# thruster_ctrl_and_pressure_sensor.net
KiCad netlist of a schematic drawn in Altium Designer
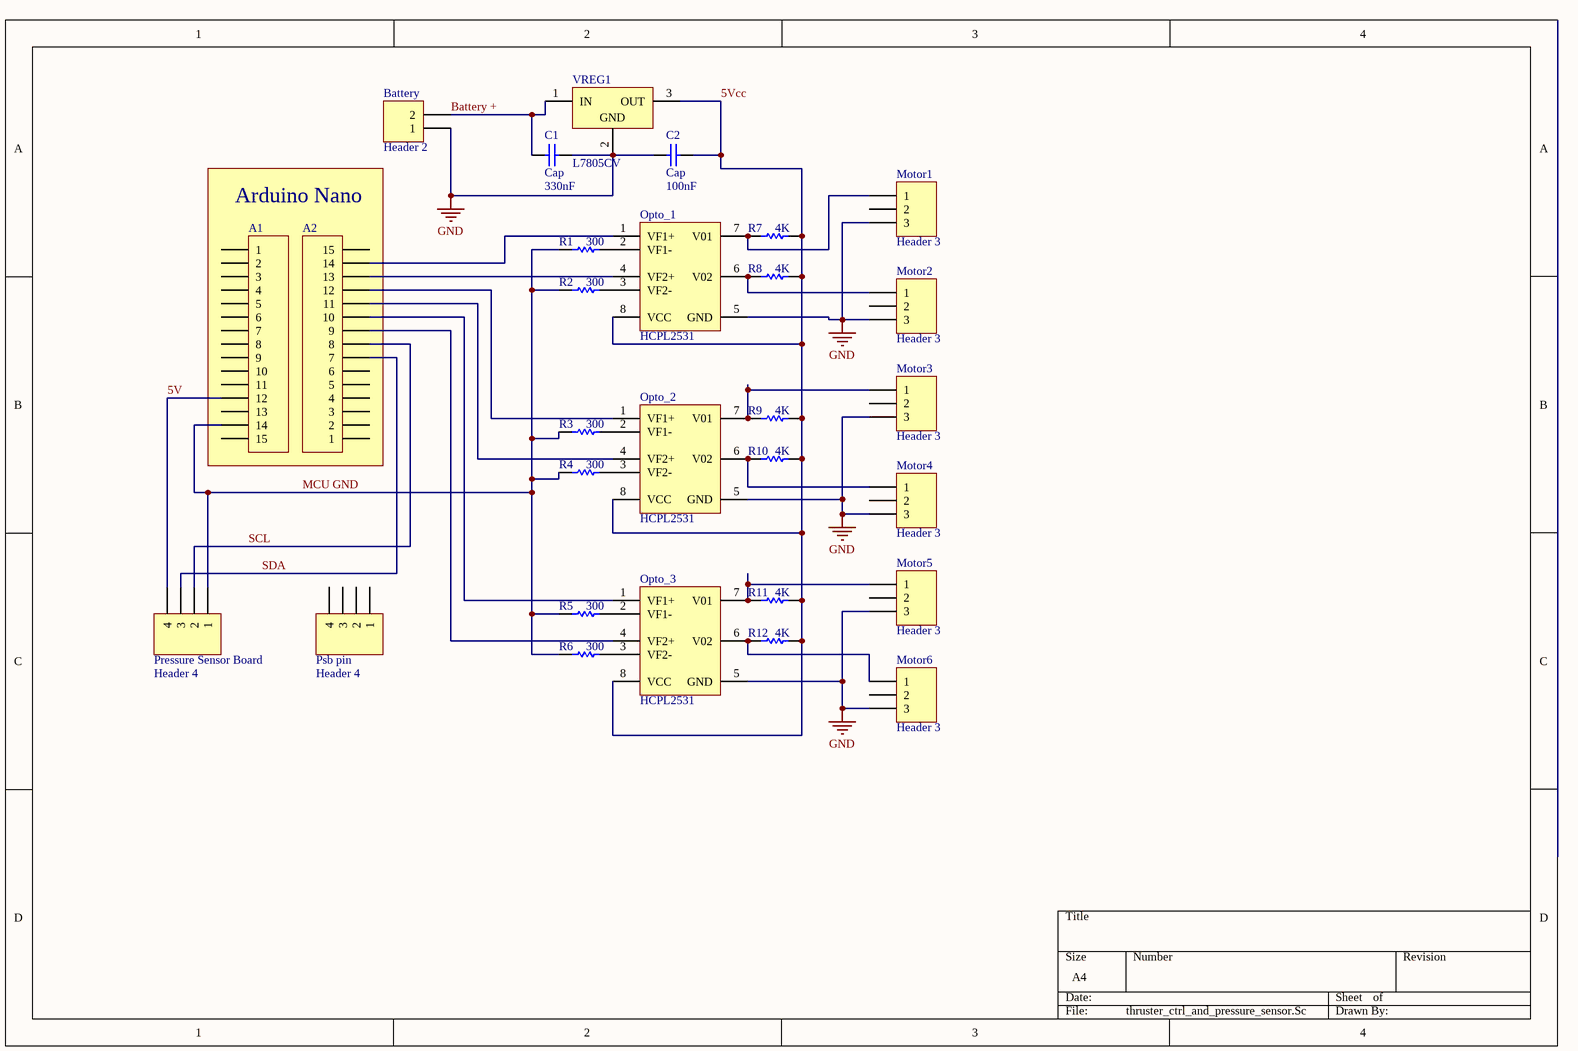
[diagram p0: thruster_ctrl_and_pressure_sensor.SchDoc]

(export (version "E")
  (design (tool "Eeschema 10.0.6"))
  (components
    (comp (ref "A1")
      (value "Header 15")
      (footprint "HDR1X15")
      (description "Header, 15-Pin")
      (fields (field (name "PUBLISHER") "Altium Limited"))
      (libsource (lib "") (part "Header 15_1"))
    )
    (comp (ref "A2")
      (value "Header 15")
      (footprint "HDR1X15")
      (description "Header, 15-Pin")
      (fields (field (name "PUBLISHER") "Altium Limited"))
      (libsource (lib "Miscellaneous Connectors") (part "Header 15"))
    )
    (comp (ref "Battery")
      (value "Header 2")
      (footprint "HDR1X2")
      (description "Header, 2-Pin")
      (fields (field (name "PUBLISHER") "Altium Limited"))
      (libsource (lib "Miscellaneous Connectors") (part "Header 2"))
    )
    (comp (ref "C1")
      (value "Cap")
      (footprint "HDR1X2")
      (description "Capacitor")
      (fields (field (name "ALTIUM_VALUE") "330nF") (field (name "PUBLISHER") "Altium Limited"))
      (libsource (lib "Miscellaneous Devices") (part "Cap"))
    )
    (comp (ref "C2")
      (value "Cap")
      (footprint "HDR1X2")
      (description "Capacitor")
      (fields (field (name "ALTIUM_VALUE") "100nF") (field (name "PUBLISHER") "Altium Limited"))
      (libsource (lib "Miscellaneous Devices") (part "Cap"))
    )
    (comp (ref "Motor1")
      (value "Header 3")
      (footprint "HDR1X3")
      (description "Header, 3-Pin")
      (fields (field (name "PUBLISHER") "Altium Limited"))
      (libsource (lib "Miscellaneous Connectors") (part "Header 3"))
    )
    (comp (ref "Motor2")
      (value "Header 3")
      (footprint "HDR1X3")
      (description "Header, 3-Pin")
      (fields (field (name "PUBLISHER") "Altium Limited"))
      (libsource (lib "Miscellaneous Connectors") (part "Header 3"))
    )
    (comp (ref "Motor3")
      (value "Header 3")
      (footprint "HDR1X3")
      (description "Header, 3-Pin")
      (fields (field (name "PUBLISHER") "Altium Limited"))
      (libsource (lib "Miscellaneous Connectors") (part "Header 3"))
    )
    (comp (ref "Motor4")
      (value "Header 3")
      (footprint "HDR1X3")
      (description "Header, 3-Pin")
      (fields (field (name "PUBLISHER") "Altium Limited"))
      (libsource (lib "Miscellaneous Connectors") (part "Header 3"))
    )
    (comp (ref "Motor5")
      (value "Header 3")
      (footprint "HDR1X3")
      (description "Header, 3-Pin")
      (fields (field (name "PUBLISHER") "Altium Limited"))
      (libsource (lib "Miscellaneous Connectors") (part "Header 3"))
    )
    (comp (ref "Motor6")
      (value "Header 3")
      (footprint "HDR1X3")
      (description "Header, 3-Pin")
      (fields (field (name "PUBLISHER") "Altium Limited"))
      (libsource (lib "Miscellaneous Connectors") (part "Header 3"))
    )
    (comp (ref "Opto_1")
      (value "HCPL2531")
      (footprint "FAIR-MDIP-8")
      (fields (field (name "MANUFACTURER") "FairchildSemiconductor"))
      (libsource (lib "Altium Content Vault") (part "FAIR-HCPL2531-DIP-8"))
    )
    (comp (ref "Opto_2")
      (value "HCPL2531")
      (footprint "FAIR-MDIP-8")
      (fields (field (name "MANUFACTURER") "FairchildSemiconductor"))
      (libsource (lib "Altium Content Vault") (part "FAIR-HCPL2531-DIP-8"))
    )
    (comp (ref "Opto_3")
      (value "HCPL2531")
      (footprint "FAIR-MDIP-8")
      (fields (field (name "MANUFACTURER") "FairchildSemiconductor"))
      (libsource (lib "Altium Content Vault") (part "FAIR-HCPL2531-DIP-8"))
    )
    (comp (ref "Pressure Sensor Board")
      (value "Header 4")
      (footprint "HDR1X4")
      (description "Header, 4-Pin")
      (fields (field (name "PUBLISHER") "Altium Limited"))
      (libsource (lib "Miscellaneous Connectors") (part "Header 4"))
    )
    (comp (ref "Psb pin")
      (value "Header 4")
      (footprint "HDR1X4")
      (description "Header, 4-Pin")
      (fields (field (name "PUBLISHER") "Altium Limited"))
      (libsource (lib "Miscellaneous Connectors") (part "Header 4"))
    )
    (comp (ref "R1")
      (value "300")
      (footprint "AXIAL-0.3")
      (description "Resistor")
      (fields (field (name "PUBLISHER") "Altium Limited"))
      (libsource (lib "Miscellaneous Devices") (part "Res1"))
    )
    (comp (ref "R2")
      (value "300")
      (footprint "AXIAL-0.3")
      (description "Resistor")
      (fields (field (name "PUBLISHER") "Altium Limited"))
      (libsource (lib "Miscellaneous Devices") (part "Res1"))
    )
    (comp (ref "R3")
      (value "300")
      (footprint "AXIAL-0.3")
      (description "Resistor")
      (fields (field (name "PUBLISHER") "Altium Limited"))
      (libsource (lib "Miscellaneous Devices") (part "Res1"))
    )
    (comp (ref "R4")
      (value "300")
      (footprint "AXIAL-0.3")
      (description "Resistor")
      (fields (field (name "PUBLISHER") "Altium Limited"))
      (libsource (lib "Miscellaneous Devices") (part "Res1"))
    )
    (comp (ref "R5")
      (value "300")
      (footprint "AXIAL-0.3")
      (description "Resistor")
      (fields (field (name "PUBLISHER") "Altium Limited"))
      (libsource (lib "Miscellaneous Devices") (part "Res1"))
    )
    (comp (ref "R6")
      (value "300")
      (footprint "AXIAL-0.3")
      (description "Resistor")
      (fields (field (name "PUBLISHER") "Altium Limited"))
      (libsource (lib "Miscellaneous Devices") (part "Res1"))
    )
    (comp (ref "R7")
      (value "4K")
      (footprint "AXIAL-0.3")
      (description "Resistor")
      (fields (field (name "Comment") "300") (field (name "PUBLISHER") "Altium Limited"))
      (libsource (lib "Miscellaneous Devices") (part "Res1"))
    )
    (comp (ref "R8")
      (value "4K")
      (footprint "AXIAL-0.3")
      (description "Resistor")
      (fields (field (name "Comment") "300") (field (name "PUBLISHER") "Altium Limited"))
      (libsource (lib "Miscellaneous Devices") (part "Res1"))
    )
    (comp (ref "R9")
      (value "4K")
      (footprint "AXIAL-0.3")
      (description "Resistor")
      (fields (field (name "Comment") "300") (field (name "PUBLISHER") "Altium Limited"))
      (libsource (lib "Miscellaneous Devices") (part "Res1"))
    )
    (comp (ref "R10")
      (value "4K")
      (footprint "AXIAL-0.3")
      (description "Resistor")
      (fields (field (name "Comment") "300") (field (name "PUBLISHER") "Altium Limited"))
      (libsource (lib "Miscellaneous Devices") (part "Res1"))
    )
    (comp (ref "R11")
      (value "4K")
      (footprint "AXIAL-0.3")
      (description "Resistor")
      (fields (field (name "Comment") "300") (field (name "PUBLISHER") "Altium Limited"))
      (libsource (lib "Miscellaneous Devices") (part "Res1"))
    )
    (comp (ref "R12")
      (value "4K")
      (footprint "AXIAL-0.3")
      (description "Resistor")
      (fields (field (name "Comment") "300") (field (name "PUBLISHER") "Altium Limited"))
      (libsource (lib "Miscellaneous Devices") (part "Res1"))
    )
    (comp (ref "VREG1")
      (value "L7805CV")
      (footprint "TO220")
      (description "Positive Voltage Regulator, 5V, 3-Pin TO-220")
      (libsource (lib "Altium Content Vault") (part "PM-REG-L4940-SIL3"))
    )
  )
  (nets
    (net (code "1") (name "/5V") (class "Default")
      (node (ref "A1") (pin "12") (pinfunction "12_12") (pintype "passive"))
      (node (ref "Pressure Sensor Board") (pin "4") (pinfunction "4_4") (pintype "passive"))
    )
    (net (code "2") (name "/5Vcc") (class "Default")
      (node (ref "C2") (pin "2") (pinfunction "2_2") (pintype "passive"))
      (node (ref "Opto_1") (pin "8") (pinfunction "VCC_8") (pintype "power_in"))
      (node (ref "Opto_2") (pin "8") (pinfunction "VCC_8") (pintype "power_in"))
      (node (ref "Opto_3") (pin "8") (pinfunction "VCC_8") (pintype "power_in"))
      (node (ref "R10") (pin "2") (pinfunction "2_2") (pintype "passive"))
      (node (ref "R11") (pin "2") (pinfunction "2_2") (pintype "passive"))
      (node (ref "R12") (pin "2") (pinfunction "2_2") (pintype "passive"))
      (node (ref "R7") (pin "2") (pinfunction "2_2") (pintype "passive"))
      (node (ref "R8") (pin "2") (pinfunction "2_2") (pintype "passive"))
      (node (ref "R9") (pin "2") (pinfunction "2_2") (pintype "passive"))
      (node (ref "VREG1") (pin "3") (pinfunction "OUT_3") (pintype "power_in"))
    )
    (net (code "3") (name "/Battery +") (class "Default")
      (node (ref "Battery") (pin "2") (pinfunction "2_2") (pintype "passive"))
      (node (ref "C1") (pin "1") (pinfunction "1_1") (pintype "passive"))
      (node (ref "VREG1") (pin "1") (pinfunction "IN_1") (pintype "power_in"))
    )
    (net (code "4") (name "/MCU GND") (class "Default")
      (node (ref "A1") (pin "14") (pinfunction "14_14") (pintype "passive"))
      (node (ref "Pressure Sensor Board") (pin "1") (pinfunction "1_1") (pintype "passive"))
      (node (ref "R1") (pin "1") (pinfunction "1_1") (pintype "passive"))
      (node (ref "R2") (pin "1") (pinfunction "1_1") (pintype "passive"))
      (node (ref "R3") (pin "1") (pinfunction "1_1") (pintype "passive"))
      (node (ref "R4") (pin "1") (pinfunction "1_1") (pintype "passive"))
      (node (ref "R5") (pin "1") (pinfunction "1_1") (pintype "passive"))
      (node (ref "R6") (pin "1") (pinfunction "1_1") (pintype "passive"))
    )
    (net (code "5") (name "/SCL") (class "Default")
      (node (ref "A2") (pin "8") (pinfunction "8_8") (pintype "passive"))
      (node (ref "Pressure Sensor Board") (pin "2") (pinfunction "2_2") (pintype "passive"))
    )
    (net (code "6") (name "/SDA") (class "Default")
      (node (ref "A2") (pin "7") (pinfunction "7_7") (pintype "passive"))
      (node (ref "Pressure Sensor Board") (pin "3") (pinfunction "3_3") (pintype "passive"))
    )
    (net (code "7") (name "GND") (class "Default")
      (node (ref "Battery") (pin "1") (pinfunction "1_1") (pintype "passive"))
      (node (ref "C1") (pin "2") (pinfunction "2_2") (pintype "passive"))
      (node (ref "C2") (pin "1") (pinfunction "1_1") (pintype "passive"))
      (node (ref "Motor1") (pin "3") (pinfunction "3_3") (pintype "passive"))
      (node (ref "Motor2") (pin "3") (pinfunction "3_3") (pintype "passive"))
      (node (ref "Motor3") (pin "3") (pinfunction "3_3") (pintype "passive"))
      (node (ref "Motor4") (pin "3") (pinfunction "3_3") (pintype "passive"))
      (node (ref "Motor5") (pin "3") (pinfunction "3_3") (pintype "passive"))
      (node (ref "Motor6") (pin "3") (pinfunction "3_3") (pintype "passive"))
      (node (ref "Opto_1") (pin "5") (pinfunction "GND_5") (pintype "power_in"))
      (node (ref "Opto_2") (pin "5") (pinfunction "GND_5") (pintype "power_in"))
      (node (ref "Opto_3") (pin "5") (pinfunction "GND_5") (pintype "power_in"))
      (node (ref "VREG1") (pin "2") (pinfunction "GND_2") (pintype "power_in"))
    )
    (net (code "8") (name "Net-(Opto_1-V01)") (class "Default")
      (node (ref "Motor1") (pin "1") (pinfunction "1_1") (pintype "passive"))
      (node (ref "Opto_1") (pin "7") (pinfunction "V01_7") (pintype "passive"))
      (node (ref "R7") (pin "1") (pinfunction "1_1") (pintype "passive"))
    )
    (net (code "9") (name "Net-(Opto_1-V02)") (class "Default")
      (node (ref "Motor2") (pin "1") (pinfunction "1_1") (pintype "passive"))
      (node (ref "Opto_1") (pin "6") (pinfunction "V02_6") (pintype "passive"))
      (node (ref "R8") (pin "1") (pinfunction "1_1") (pintype "passive"))
    )
    (net (code "10") (name "Net-(Opto_1-VF1+)") (class "Default")
      (node (ref "A2") (pin "14") (pinfunction "14_14") (pintype "passive"))
      (node (ref "Opto_1") (pin "1") (pinfunction "VF1+_1") (pintype "passive"))
    )
    (net (code "11") (name "Net-(Opto_1-VF1-)") (class "Default")
      (node (ref "Opto_1") (pin "2") (pinfunction "VF1-_2") (pintype "passive"))
      (node (ref "R1") (pin "2") (pinfunction "2_2") (pintype "passive"))
    )
    (net (code "12") (name "Net-(Opto_1-VF2+)") (class "Default")
      (node (ref "A2") (pin "13") (pinfunction "13_13") (pintype "passive"))
      (node (ref "Opto_1") (pin "4") (pinfunction "VF2+_4") (pintype "passive"))
    )
    (net (code "13") (name "Net-(Opto_1-VF2-)") (class "Default")
      (node (ref "Opto_1") (pin "3") (pinfunction "VF2-_3") (pintype "passive"))
      (node (ref "R2") (pin "2") (pinfunction "2_2") (pintype "passive"))
    )
    (net (code "14") (name "Net-(Opto_2-V01)") (class "Default")
      (node (ref "Motor3") (pin "1") (pinfunction "1_1") (pintype "passive"))
      (node (ref "Opto_2") (pin "7") (pinfunction "V01_7") (pintype "passive"))
      (node (ref "R9") (pin "1") (pinfunction "1_1") (pintype "passive"))
    )
    (net (code "15") (name "Net-(Opto_2-V02)") (class "Default")
      (node (ref "Motor4") (pin "1") (pinfunction "1_1") (pintype "passive"))
      (node (ref "Opto_2") (pin "6") (pinfunction "V02_6") (pintype "passive"))
      (node (ref "R10") (pin "1") (pinfunction "1_1") (pintype "passive"))
    )
    (net (code "16") (name "Net-(Opto_2-VF1+)") (class "Default")
      (node (ref "A2") (pin "12") (pinfunction "12_12") (pintype "passive"))
      (node (ref "Opto_2") (pin "1") (pinfunction "VF1+_1") (pintype "passive"))
    )
    (net (code "17") (name "Net-(Opto_2-VF1-)") (class "Default")
      (node (ref "Opto_2") (pin "2") (pinfunction "VF1-_2") (pintype "passive"))
      (node (ref "R3") (pin "2") (pinfunction "2_2") (pintype "passive"))
    )
    (net (code "18") (name "Net-(Opto_2-VF2+)") (class "Default")
      (node (ref "A2") (pin "11") (pinfunction "11_11") (pintype "passive"))
      (node (ref "Opto_2") (pin "4") (pinfunction "VF2+_4") (pintype "passive"))
    )
    (net (code "19") (name "Net-(Opto_2-VF2-)") (class "Default")
      (node (ref "Opto_2") (pin "3") (pinfunction "VF2-_3") (pintype "passive"))
      (node (ref "R4") (pin "2") (pinfunction "2_2") (pintype "passive"))
    )
    (net (code "20") (name "Net-(Opto_3-V01)") (class "Default")
      (node (ref "Motor5") (pin "1") (pinfunction "1_1") (pintype "passive"))
      (node (ref "Opto_3") (pin "7") (pinfunction "V01_7") (pintype "passive"))
      (node (ref "R11") (pin "1") (pinfunction "1_1") (pintype "passive"))
    )
    (net (code "21") (name "Net-(Opto_3-V02)") (class "Default")
      (node (ref "Motor6") (pin "1") (pinfunction "1_1") (pintype "passive"))
      (node (ref "Opto_3") (pin "6") (pinfunction "V02_6") (pintype "passive"))
      (node (ref "R12") (pin "1") (pinfunction "1_1") (pintype "passive"))
    )
    (net (code "22") (name "Net-(Opto_3-VF1+)") (class "Default")
      (node (ref "A2") (pin "10") (pinfunction "10_10") (pintype "passive"))
      (node (ref "Opto_3") (pin "1") (pinfunction "VF1+_1") (pintype "passive"))
    )
    (net (code "23") (name "Net-(Opto_3-VF1-)") (class "Default")
      (node (ref "Opto_3") (pin "2") (pinfunction "VF1-_2") (pintype "passive"))
      (node (ref "R5") (pin "2") (pinfunction "2_2") (pintype "passive"))
    )
    (net (code "24") (name "Net-(Opto_3-VF2+)") (class "Default")
      (node (ref "A2") (pin "9") (pinfunction "9_9") (pintype "passive"))
      (node (ref "Opto_3") (pin "4") (pinfunction "VF2+_4") (pintype "passive"))
    )
    (net (code "25") (name "Net-(Opto_3-VF2-)") (class "Default")
      (node (ref "Opto_3") (pin "3") (pinfunction "VF2-_3") (pintype "passive"))
      (node (ref "R6") (pin "2") (pinfunction "2_2") (pintype "passive"))
    )
    (net (code "26") (name "unconnected-(A1-Pad1)") (class "Default")
      (node (ref "A1") (pin "1") (pinfunction "1_1") (pintype "passive"))
    )
    (net (code "27") (name "unconnected-(A1-Pad2)") (class "Default")
      (node (ref "A1") (pin "2") (pinfunction "2_2") (pintype "passive"))
    )
    (net (code "28") (name "unconnected-(A1-Pad3)") (class "Default")
      (node (ref "A1") (pin "3") (pinfunction "3_3") (pintype "passive"))
    )
    (net (code "29") (name "unconnected-(A1-Pad4)") (class "Default")
      (node (ref "A1") (pin "4") (pinfunction "4_4") (pintype "passive"))
    )
    (net (code "30") (name "unconnected-(A1-Pad5)") (class "Default")
      (node (ref "A1") (pin "5") (pinfunction "5_5") (pintype "passive"))
    )
    (net (code "31") (name "unconnected-(A1-Pad6)") (class "Default")
      (node (ref "A1") (pin "6") (pinfunction "6_6") (pintype "passive"))
    )
    (net (code "32") (name "unconnected-(A1-Pad7)") (class "Default")
      (node (ref "A1") (pin "7") (pinfunction "7_7") (pintype "passive"))
    )
    (net (code "33") (name "unconnected-(A1-Pad8)") (class "Default")
      (node (ref "A1") (pin "8") (pinfunction "8_8") (pintype "passive"))
    )
    (net (code "34") (name "unconnected-(A1-Pad9)") (class "Default")
      (node (ref "A1") (pin "9") (pinfunction "9_9") (pintype "passive"))
    )
    (net (code "35") (name "unconnected-(A1-Pad10)") (class "Default")
      (node (ref "A1") (pin "10") (pinfunction "10_10") (pintype "passive"))
    )
    (net (code "36") (name "unconnected-(A1-Pad11)") (class "Default")
      (node (ref "A1") (pin "11") (pinfunction "11_11") (pintype "passive"))
    )
    (net (code "37") (name "unconnected-(A1-Pad13)") (class "Default")
      (node (ref "A1") (pin "13") (pinfunction "13_13") (pintype "passive"))
    )
    (net (code "38") (name "unconnected-(A1-Pad15)") (class "Default")
      (node (ref "A1") (pin "15") (pinfunction "15_15") (pintype "passive"))
    )
    (net (code "39") (name "unconnected-(A2-Pad1)") (class "Default")
      (node (ref "A2") (pin "1") (pinfunction "1_1") (pintype "passive"))
    )
    (net (code "40") (name "unconnected-(A2-Pad2)") (class "Default")
      (node (ref "A2") (pin "2") (pinfunction "2_2") (pintype "passive"))
    )
    (net (code "41") (name "unconnected-(A2-Pad3)") (class "Default")
      (node (ref "A2") (pin "3") (pinfunction "3_3") (pintype "passive"))
    )
    (net (code "42") (name "unconnected-(A2-Pad4)") (class "Default")
      (node (ref "A2") (pin "4") (pinfunction "4_4") (pintype "passive"))
    )
    (net (code "43") (name "unconnected-(A2-Pad5)") (class "Default")
      (node (ref "A2") (pin "5") (pinfunction "5_5") (pintype "passive"))
    )
    (net (code "44") (name "unconnected-(A2-Pad6)") (class "Default")
      (node (ref "A2") (pin "6") (pinfunction "6_6") (pintype "passive"))
    )
    (net (code "45") (name "unconnected-(A2-Pad15)") (class "Default")
      (node (ref "A2") (pin "15") (pinfunction "15_15") (pintype "passive"))
    )
    (net (code "46") (name "unconnected-(Motor1-Pad2)") (class "Default")
      (node (ref "Motor1") (pin "2") (pinfunction "2_2") (pintype "passive"))
    )
    (net (code "47") (name "unconnected-(Motor2-Pad2)") (class "Default")
      (node (ref "Motor2") (pin "2") (pinfunction "2_2") (pintype "passive"))
    )
    (net (code "48") (name "unconnected-(Motor3-Pad2)") (class "Default")
      (node (ref "Motor3") (pin "2") (pinfunction "2_2") (pintype "passive"))
    )
    (net (code "49") (name "unconnected-(Motor4-Pad2)") (class "Default")
      (node (ref "Motor4") (pin "2") (pinfunction "2_2") (pintype "passive"))
    )
    (net (code "50") (name "unconnected-(Motor5-Pad2)") (class "Default")
      (node (ref "Motor5") (pin "2") (pinfunction "2_2") (pintype "passive"))
    )
    (net (code "51") (name "unconnected-(Motor6-Pad2)") (class "Default")
      (node (ref "Motor6") (pin "2") (pinfunction "2_2") (pintype "passive"))
    )
    (net (code "52") (name "unconnected-(Psb pin-Pad1)") (class "Default")
      (node (ref "Psb pin") (pin "1") (pinfunction "1_1") (pintype "passive"))
    )
    (net (code "53") (name "unconnected-(Psb pin-Pad2)") (class "Default")
      (node (ref "Psb pin") (pin "2") (pinfunction "2_2") (pintype "passive"))
    )
    (net (code "54") (name "unconnected-(Psb pin-Pad3)") (class "Default")
      (node (ref "Psb pin") (pin "3") (pinfunction "3_3") (pintype "passive"))
    )
    (net (code "55") (name "unconnected-(Psb pin-Pad4)") (class "Default")
      (node (ref "Psb pin") (pin "4") (pinfunction "4_4") (pintype "passive"))
    )
  )
)
